# maclight-v2.net
KiCad netlist of a schematic drawn in EAGLE
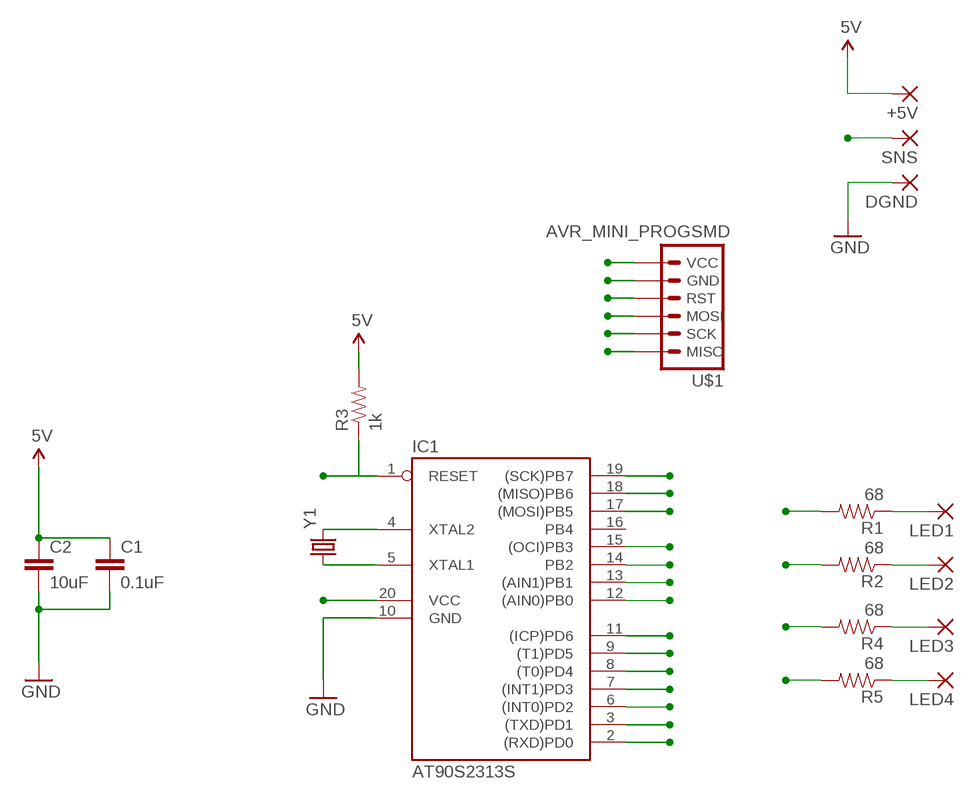
[diagram p0: schematic, sheet 1]

(export (version "E")
  (design (tool "Eeschema 10.0.6"))
  (components
    (comp (ref "+5V")
      (value "SMD2")
      (footprint "eagle-import:SMD1,27-2,54")
      (libsource (lib "eagle-import") (part "SMD2"))
    )
    (comp (ref "C1")
      (value "0.1uF")
      (footprint "eagle-import:0805")
      (libsource (lib "eagle-import") (part "CAP0805"))
    )
    (comp (ref "C2")
      (value "10uF")
      (footprint "eagle-import:1210")
      (libsource (lib "eagle-import") (part "CAP1210"))
    )
    (comp (ref "DGND")
      (value "SMD2")
      (footprint "eagle-import:SMD1,27-2,54")
      (libsource (lib "eagle-import") (part "SMD2"))
    )
    (comp (ref "IC1")
      (value "AT90S2313S")
      (footprint "eagle-import:SO20L")
      (libsource (lib "eagle-import") (part "AT90S2313S"))
    )
    (comp (ref "LED1")
      (value "SMD2")
      (footprint "eagle-import:SMD1,27-2,54")
      (libsource (lib "eagle-import") (part "SMD2"))
    )
    (comp (ref "LED2")
      (value "SMD2")
      (footprint "eagle-import:SMD1,27-2,54")
      (libsource (lib "eagle-import") (part "SMD2"))
    )
    (comp (ref "LED3")
      (value "SMD2")
      (footprint "eagle-import:SMD1,27-2,54")
      (libsource (lib "eagle-import") (part "SMD2"))
    )
    (comp (ref "LED4")
      (value "SMD2")
      (footprint "eagle-import:SMD1,27-2,54")
      (libsource (lib "eagle-import") (part "SMD2"))
    )
    (comp (ref "R1")
      (value "68")
      (footprint "eagle-import:0805")
      (libsource (lib "eagle-import") (part "RESISTOR0805-RES"))
    )
    (comp (ref "R2")
      (value "68")
      (footprint "eagle-import:0805")
      (libsource (lib "eagle-import") (part "RESISTOR0805-RES"))
    )
    (comp (ref "R3")
      (value "1k")
      (footprint "eagle-import:0805")
      (libsource (lib "eagle-import") (part "RESISTOR0805-RES"))
    )
    (comp (ref "R4")
      (value "68")
      (footprint "eagle-import:0805")
      (libsource (lib "eagle-import") (part "RESISTOR0805-RES"))
    )
    (comp (ref "R5")
      (value "68")
      (footprint "eagle-import:0805")
      (libsource (lib "eagle-import") (part "RESISTOR0805-RES"))
    )
    (comp (ref "SNS")
      (value "SMD2")
      (footprint "eagle-import:SMD1,27-2,54")
      (libsource (lib "eagle-import") (part "SMD2"))
    )
    (comp (ref "U$1")
      (value "AVR_MINI_PROGSMD")
      (footprint "eagle-import:AVR_MINI_PROG")
      (libsource (lib "eagle-import") (part "AVR_MINI_PROGSMD"))
    )
    (comp (ref "Y1")
      (value "CRYSTAL5X3")
      (footprint "eagle-import:CRYSTAL-SMD-5X3")
      (libsource (lib "eagle-import") (part "CRYSTAL5X3"))
    )
  )
  (nets
    (net (code "1") (name "/LED1") (class "Default")
      (node (ref "IC1") (pin "12") (pinfunction "(AIN0)PB0_12") (pintype "bidirectional"))
      (node (ref "R1") (pin "2") (pinfunction "2_2") (pintype "passive"))
    )
    (net (code "2") (name "/LED2") (class "Default")
      (node (ref "IC1") (pin "13") (pinfunction "(AIN1)PB1_13") (pintype "bidirectional"))
      (node (ref "R2") (pin "2") (pinfunction "2_2") (pintype "passive"))
    )
    (net (code "3") (name "/LED3") (class "Default")
      (node (ref "IC1") (pin "14") (pinfunction "PB2_14") (pintype "bidirectional"))
      (node (ref "R4") (pin "2") (pinfunction "2_2") (pintype "passive"))
    )
    (net (code "4") (name "/LED4") (class "Default")
      (node (ref "IC1") (pin "15") (pinfunction "(OCI)PB3_15") (pintype "bidirectional"))
      (node (ref "R5") (pin "2") (pinfunction "2_2") (pintype "passive"))
    )
    (net (code "5") (name "/MISO") (class "Default")
      (node (ref "IC1") (pin "18") (pinfunction "(MISO)PB6_18") (pintype "bidirectional"))
      (node (ref "U$1") (pin "6") (pinfunction "MISO_6") (pintype "passive"))
    )
    (net (code "6") (name "/MOSI{slash}SDA") (class "Default")
      (node (ref "IC1") (pin "17") (pinfunction "(MOSI)PB5_17") (pintype "bidirectional"))
      (node (ref "U$1") (pin "4") (pinfunction "MOSI_4") (pintype "passive"))
    )
    (net (code "7") (name "/PWR_SENSE") (class "Default")
      (node (ref "IC1") (pin "6") (pinfunction "(INT0)PD2_6") (pintype "bidirectional"))
      (node (ref "SNS") (pin "1") (pinfunction "P_1") (pintype "passive"))
    )
    (net (code "8") (name "/RESET") (class "Default")
      (node (ref "IC1") (pin "1") (pinfunction "RESET_1") (pintype "bidirectional"))
      (node (ref "R3") (pin "1") (pinfunction "1_1") (pintype "passive"))
      (node (ref "U$1") (pin "3") (pinfunction "RST_3") (pintype "passive"))
    )
    (net (code "9") (name "/SCK{slash}SCL") (class "Default")
      (node (ref "IC1") (pin "19") (pinfunction "(SCK)PB7_19") (pintype "bidirectional"))
      (node (ref "U$1") (pin "5") (pinfunction "SCK_5") (pintype "passive"))
    )
    (net (code "10") (name "5V") (class "Default")
      (node (ref "+5V") (pin "1") (pinfunction "P_1") (pintype "passive"))
      (node (ref "C1") (pin "1") (pinfunction "1_1") (pintype "passive"))
      (node (ref "C2") (pin "1") (pinfunction "1_1") (pintype "passive"))
      (node (ref "IC1") (pin "20") (pinfunction "VCC_20") (pintype "power_in"))
      (node (ref "R3") (pin "2") (pinfunction "2_2") (pintype "passive"))
      (node (ref "U$1") (pin "1") (pinfunction "VCC_1") (pintype "passive"))
    )
    (net (code "11") (name "GND") (class "Default")
      (node (ref "C1") (pin "2") (pinfunction "2_2") (pintype "passive"))
      (node (ref "C2") (pin "2") (pinfunction "2_2") (pintype "passive"))
      (node (ref "DGND") (pin "1") (pinfunction "P_1") (pintype "passive"))
      (node (ref "IC1") (pin "10") (pinfunction "GND_10") (pintype "power_in"))
      (node (ref "U$1") (pin "2") (pinfunction "GND_2") (pintype "passive"))
    )
    (net (code "12") (name "Net-(IC1-XTAL1)") (class "Default")
      (node (ref "IC1") (pin "5") (pinfunction "XTAL1_5") (pintype "bidirectional"))
      (node (ref "Y1") (pin "1") (pinfunction "1_1") (pintype "passive"))
    )
    (net (code "13") (name "Net-(IC1-XTAL2)") (class "Default")
      (node (ref "IC1") (pin "4") (pinfunction "XTAL2_4") (pintype "bidirectional"))
      (node (ref "Y1") (pin "3") (pinfunction "2_3") (pintype "passive"))
    )
    (net (code "14") (name "Net-(LED1-P)") (class "Default")
      (node (ref "LED1") (pin "1") (pinfunction "P_1") (pintype "passive"))
      (node (ref "R1") (pin "1") (pinfunction "1_1") (pintype "passive"))
    )
    (net (code "15") (name "Net-(LED2-P)") (class "Default")
      (node (ref "LED2") (pin "1") (pinfunction "P_1") (pintype "passive"))
      (node (ref "R2") (pin "1") (pinfunction "1_1") (pintype "passive"))
    )
    (net (code "16") (name "Net-(LED3-P)") (class "Default")
      (node (ref "LED3") (pin "1") (pinfunction "P_1") (pintype "passive"))
      (node (ref "R4") (pin "1") (pinfunction "1_1") (pintype "passive"))
    )
    (net (code "17") (name "Net-(LED4-P)") (class "Default")
      (node (ref "LED4") (pin "1") (pinfunction "P_1") (pintype "passive"))
      (node (ref "R5") (pin "1") (pinfunction "1_1") (pintype "passive"))
    )
    (net (code "18") (name "unconnected-(IC1-(ICP)PD6-Pad11)") (class "Default")
      (node (ref "IC1") (pin "11") (pinfunction "(ICP)PD6_11") (pintype "bidirectional"))
    )
    (net (code "19") (name "unconnected-(IC1-(INT1)PD3-Pad7)") (class "Default")
      (node (ref "IC1") (pin "7") (pinfunction "(INT1)PD3_7") (pintype "bidirectional"))
    )
    (net (code "20") (name "unconnected-(IC1-(RXD)PD0-Pad2)") (class "Default")
      (node (ref "IC1") (pin "2") (pinfunction "(RXD)PD0_2") (pintype "bidirectional"))
    )
    (net (code "21") (name "unconnected-(IC1-(T0)PD4-Pad8)") (class "Default")
      (node (ref "IC1") (pin "8") (pinfunction "(T0)PD4_8") (pintype "bidirectional"))
    )
    (net (code "22") (name "unconnected-(IC1-(T1)PD5-Pad9)") (class "Default")
      (node (ref "IC1") (pin "9") (pinfunction "(T1)PD5_9") (pintype "bidirectional"))
    )
    (net (code "23") (name "unconnected-(IC1-(TXD)PD1-Pad3)") (class "Default")
      (node (ref "IC1") (pin "3") (pinfunction "(TXD)PD1_3") (pintype "bidirectional"))
    )
    (net (code "24") (name "unconnected-(IC1-PB4-Pad16)") (class "Default")
      (node (ref "IC1") (pin "16") (pinfunction "PB4_16") (pintype "bidirectional"))
    )
  )
)
